# signalamp.net
KiCad netlist of a schematic drawn in EAGLE
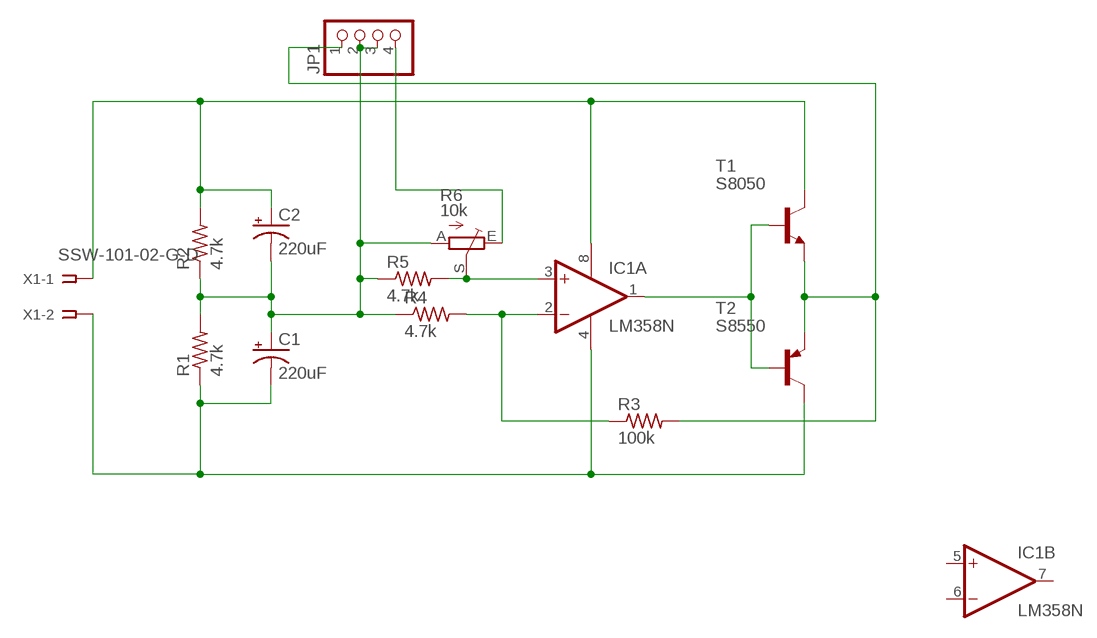
[diagram p0: schematic, sheet 1]

(export (version "E")
  (design (tool "Eeschema 10.0.6"))
  (components
    (comp (ref "C1")
      (value "220uF")
      (footprint "eagle-import:E2-5")
      (libsource (lib "eagle-import") (part "CPOL-USE2-5"))
    )
    (comp (ref "C2")
      (value "220uF")
      (footprint "eagle-import:E2-5")
      (libsource (lib "eagle-import") (part "CPOL-USE2-5"))
    )
    (comp (ref "IC1")
      (value "LM358N")
      (footprint "eagle-import:DIL08")
      (fields (field (name "SPICEPREFIX") "B"))
      (libsource (lib "eagle-import") (part "LM358N"))
    )
    (comp (ref "JP1")
      (value "PINHD-1X4")
      (footprint "eagle-import:1X04")
      (libsource (lib "eagle-import") (part "PINHD-1X4"))
    )
    (comp (ref "R1")
      (value "4.7k")
      (footprint "eagle-import:0204_7")
      (libsource (lib "eagle-import") (part "R-US_0204/7"))
    )
    (comp (ref "R2")
      (value "4.7k")
      (footprint "eagle-import:0204_7")
      (libsource (lib "eagle-import") (part "R-US_0204/7"))
    )
    (comp (ref "R3")
      (value "100k")
      (footprint "eagle-import:0207_5V")
      (libsource (lib "eagle-import") (part "R-US_0207/5V"))
    )
    (comp (ref "R4")
      (value "4.7k")
      (footprint "eagle-import:0204_7")
      (libsource (lib "eagle-import") (part "R-US_0204/7"))
    )
    (comp (ref "R5")
      (value "4.7k")
      (footprint "eagle-import:0207_2V")
      (libsource (lib "eagle-import") (part "R-US_0207/2V"))
    )
    (comp (ref "R6")
      (value "10k")
      (footprint "eagle-import:S64W")
      (libsource (lib "eagle-import") (part "TRIM_EU-S64W"))
    )
    (comp (ref "T1")
      (value "S8050")
      (footprint "eagle-import:TO92-EBC")
      (fields (field (name "SPICEPREFIX") "J"))
      (libsource (lib "eagle-import") (part "-NPN-TO92-EBC"))
    )
    (comp (ref "T2")
      (value "S8550")
      (footprint "eagle-import:TO92-EBC")
      (libsource (lib "eagle-import") (part "-PNP-TO92-EBCBC558B"))
    )
    (comp (ref "X1")
      (value "SSW-101-02-G-D")
      (footprint "eagle-import:SSW-101-02-G-D")
      (fields (field (name "MF") "Samtec Inc.") (field (name "SPICEPREFIX") "X"))
      (libsource (lib "eagle-import") (part "SSW-101-02-G-D"))
    )
  )
  (nets
    (net (code "1") (name "Net-(C1-Pad+)") (class "Default")
      (node (ref "C1") (pin "+") (pinfunction "+_+") (pintype "passive"))
      (node (ref "C2") (pin "-") (pinfunction "-_-") (pintype "passive"))
      (node (ref "JP1") (pin "2") (pinfunction "2_2") (pintype "passive"))
      (node (ref "JP1") (pin "3") (pinfunction "3_3") (pintype "passive"))
      (node (ref "R1") (pin "2") (pinfunction "2_2") (pintype "passive"))
      (node (ref "R2") (pin "1") (pinfunction "1_1") (pintype "passive"))
      (node (ref "R4") (pin "1") (pinfunction "1_1") (pintype "passive"))
      (node (ref "R5") (pin "1") (pinfunction "1_1") (pintype "passive"))
      (node (ref "R6") (pin "A") (pinfunction "A_A") (pintype "passive"))
    )
    (net (code "2") (name "Net-(IC1A-+IN)") (class "Default")
      (node (ref "IC1") (pin "3") (pinfunction "+IN_3") (pintype "input"))
      (node (ref "R5") (pin "2") (pinfunction "2_2") (pintype "passive"))
      (node (ref "R6") (pin "S") (pinfunction "S_S") (pintype "passive"))
    )
    (net (code "3") (name "Net-(IC1A--IN)") (class "Default")
      (node (ref "IC1") (pin "2") (pinfunction "-IN_2") (pintype "input"))
      (node (ref "R3") (pin "1") (pinfunction "1_1") (pintype "passive"))
      (node (ref "R4") (pin "2") (pinfunction "2_2") (pintype "passive"))
    )
    (net (code "4") (name "Net-(IC1A-OUT)") (class "Default")
      (node (ref "IC1") (pin "1") (pinfunction "OUT_1") (pintype "output"))
      (node (ref "T1") (pin "B") (pinfunction "B_B") (pintype "passive"))
      (node (ref "T2") (pin "B") (pinfunction "B_B") (pintype "passive"))
    )
    (net (code "5") (name "Net-(IC1C-V+)") (class "Default")
      (node (ref "C2") (pin "+") (pinfunction "+_+") (pintype "passive"))
      (node (ref "IC1") (pin "8") (pinfunction "V+_8") (pintype "power_in"))
      (node (ref "R2") (pin "2") (pinfunction "2_2") (pintype "passive"))
      (node (ref "T1") (pin "C") (pinfunction "C_C") (pintype "passive"))
      (node (ref "X1") (pin "1") (pinfunction "1_1") (pintype "passive"))
    )
    (net (code "6") (name "Net-(IC1C-V-)") (class "Default")
      (node (ref "C1") (pin "-") (pinfunction "-_-") (pintype "passive"))
      (node (ref "IC1") (pin "4") (pinfunction "V-_4") (pintype "power_in"))
      (node (ref "R1") (pin "1") (pinfunction "1_1") (pintype "passive"))
      (node (ref "T2") (pin "C") (pinfunction "C_C") (pintype "passive"))
      (node (ref "X1") (pin "2") (pinfunction "1_2") (pintype "passive"))
    )
    (net (code "7") (name "Net-(JP1-Pad1)") (class "Default")
      (node (ref "JP1") (pin "1") (pinfunction "1_1") (pintype "passive"))
      (node (ref "R3") (pin "2") (pinfunction "2_2") (pintype "passive"))
      (node (ref "T1") (pin "E") (pinfunction "E_E") (pintype "passive"))
      (node (ref "T2") (pin "E") (pinfunction "E_E") (pintype "passive"))
    )
    (net (code "8") (name "Net-(JP1-Pad4)") (class "Default")
      (node (ref "JP1") (pin "4") (pinfunction "4_4") (pintype "passive"))
      (node (ref "R6") (pin "E") (pinfunction "E_E") (pintype "passive"))
    )
    (net (code "9") (name "unconnected-(IC1B-+IN-Pad5)") (class "Default")
      (node (ref "IC1") (pin "5") (pinfunction "+IN_5") (pintype "input"))
    )
    (net (code "10") (name "unconnected-(IC1B--IN-Pad6)") (class "Default")
      (node (ref "IC1") (pin "6") (pinfunction "-IN_6") (pintype "input"))
    )
    (net (code "11") (name "unconnected-(IC1B-OUT-Pad7)") (class "Default")
      (node (ref "IC1") (pin "7") (pinfunction "OUT_7") (pintype "output"))
    )
  )
)
